# PROTOTYPE_A.net
KiCad netlist of a schematic drawn in Altium Designer
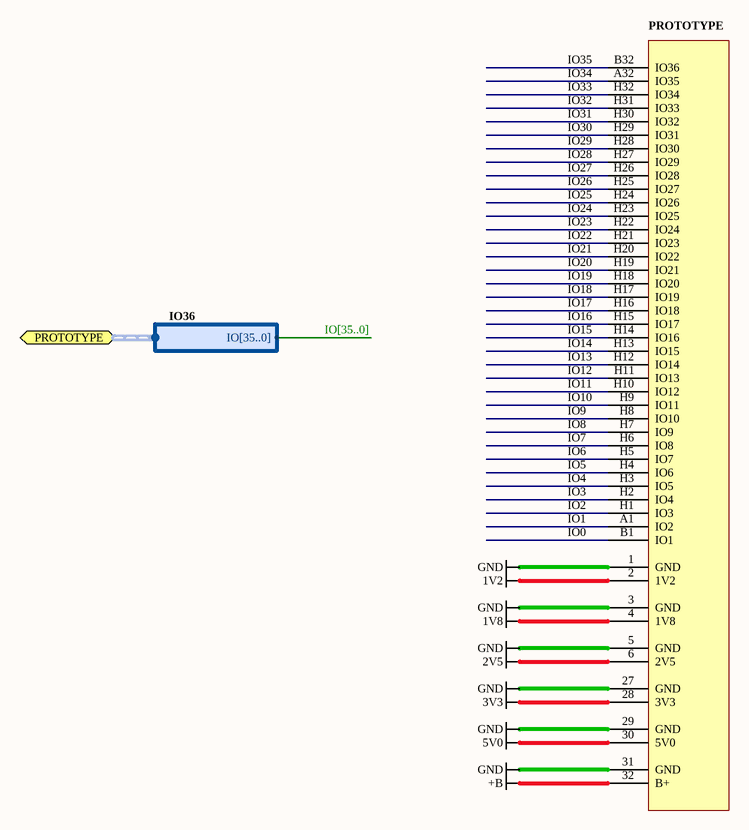
[diagram p0: PROTOTYPE_A.SchDoc]

(export (version "E")
  (design (tool "Eeschema 10.0.6"))
  (components
    (comp (ref "PROTOTYPE")
      (value "~")
      (footprint "TESTPOINT_ARRAY")
      (description "Test Point Array")
      (libsource (lib "AltiumDesignLibrary") (part "TEST-ARRAY"))
    )
  )
  (nets
    (net (code "2") (name "+B") (class "Default")
      (node (ref "PROTOTYPE") (pin "32") (pinfunction "B+_32") (pintype "power_in"))
    )
    (net (code "3") (name "/IO0") (class "Default")
      (node (ref "PROTOTYPE") (pin "B1") (pinfunction "IO1_B1") (pintype "passive"))
    )
    (net (code "4") (name "/IO1") (class "Default")
      (node (ref "PROTOTYPE") (pin "A1") (pinfunction "IO2_A1") (pintype "passive"))
    )
    (net (code "5") (name "/IO2") (class "Default")
      (node (ref "PROTOTYPE") (pin "H1") (pinfunction "IO3_H1") (pintype "passive"))
    )
    (net (code "6") (name "/IO3") (class "Default")
      (node (ref "PROTOTYPE") (pin "H2") (pinfunction "IO4_H2") (pintype "passive"))
    )
    (net (code "7") (name "/IO4") (class "Default")
      (node (ref "PROTOTYPE") (pin "H3") (pinfunction "IO5_H3") (pintype "passive"))
    )
    (net (code "8") (name "/IO5") (class "Default")
      (node (ref "PROTOTYPE") (pin "H4") (pinfunction "IO6_H4") (pintype "passive"))
    )
    (net (code "9") (name "/IO6") (class "Default")
      (node (ref "PROTOTYPE") (pin "H5") (pinfunction "IO7_H5") (pintype "passive"))
    )
    (net (code "10") (name "/IO7") (class "Default")
      (node (ref "PROTOTYPE") (pin "H6") (pinfunction "IO8_H6") (pintype "passive"))
    )
    (net (code "11") (name "/IO8") (class "Default")
      (node (ref "PROTOTYPE") (pin "H7") (pinfunction "IO9_H7") (pintype "passive"))
    )
    (net (code "12") (name "/IO9") (class "Default")
      (node (ref "PROTOTYPE") (pin "H8") (pinfunction "IO10_H8") (pintype "passive"))
    )
    (net (code "13") (name "/IO10") (class "Default")
      (node (ref "PROTOTYPE") (pin "H9") (pinfunction "IO11_H9") (pintype "passive"))
    )
    (net (code "14") (name "/IO11") (class "Default")
      (node (ref "PROTOTYPE") (pin "H10") (pinfunction "IO12_H10") (pintype "passive"))
    )
    (net (code "15") (name "/IO12") (class "Default")
      (node (ref "PROTOTYPE") (pin "H11") (pinfunction "IO13_H11") (pintype "passive"))
    )
    (net (code "16") (name "/IO13") (class "Default")
      (node (ref "PROTOTYPE") (pin "H12") (pinfunction "IO14_H12") (pintype "passive"))
    )
    (net (code "17") (name "/IO14") (class "Default")
      (node (ref "PROTOTYPE") (pin "H13") (pinfunction "IO15_H13") (pintype "passive"))
    )
    (net (code "18") (name "/IO15") (class "Default")
      (node (ref "PROTOTYPE") (pin "H14") (pinfunction "IO16_H14") (pintype "passive"))
    )
    (net (code "19") (name "/IO16") (class "Default")
      (node (ref "PROTOTYPE") (pin "H15") (pinfunction "IO17_H15") (pintype "passive"))
    )
    (net (code "20") (name "/IO17") (class "Default")
      (node (ref "PROTOTYPE") (pin "H16") (pinfunction "IO18_H16") (pintype "passive"))
    )
    (net (code "21") (name "/IO18") (class "Default")
      (node (ref "PROTOTYPE") (pin "H17") (pinfunction "IO19_H17") (pintype "passive"))
    )
    (net (code "22") (name "/IO19") (class "Default")
      (node (ref "PROTOTYPE") (pin "H18") (pinfunction "IO20_H18") (pintype "passive"))
    )
    (net (code "23") (name "/IO20") (class "Default")
      (node (ref "PROTOTYPE") (pin "H19") (pinfunction "IO21_H19") (pintype "passive"))
    )
    (net (code "24") (name "/IO21") (class "Default")
      (node (ref "PROTOTYPE") (pin "H20") (pinfunction "IO22_H20") (pintype "passive"))
    )
    (net (code "25") (name "/IO22") (class "Default")
      (node (ref "PROTOTYPE") (pin "H21") (pinfunction "IO23_H21") (pintype "passive"))
    )
    (net (code "26") (name "/IO23") (class "Default")
      (node (ref "PROTOTYPE") (pin "H22") (pinfunction "IO24_H22") (pintype "passive"))
    )
    (net (code "27") (name "/IO24") (class "Default")
      (node (ref "PROTOTYPE") (pin "H23") (pinfunction "IO25_H23") (pintype "passive"))
    )
    (net (code "28") (name "/IO25") (class "Default")
      (node (ref "PROTOTYPE") (pin "H24") (pinfunction "IO26_H24") (pintype "passive"))
    )
    (net (code "29") (name "/IO26") (class "Default")
      (node (ref "PROTOTYPE") (pin "H25") (pinfunction "IO27_H25") (pintype "passive"))
    )
    (net (code "30") (name "/IO27") (class "Default")
      (node (ref "PROTOTYPE") (pin "H26") (pinfunction "IO28_H26") (pintype "passive"))
    )
    (net (code "31") (name "/IO28") (class "Default")
      (node (ref "PROTOTYPE") (pin "H27") (pinfunction "IO29_H27") (pintype "passive"))
    )
    (net (code "32") (name "/IO29") (class "Default")
      (node (ref "PROTOTYPE") (pin "H28") (pinfunction "IO30_H28") (pintype "passive"))
    )
    (net (code "33") (name "/IO30") (class "Default")
      (node (ref "PROTOTYPE") (pin "H29") (pinfunction "IO31_H29") (pintype "passive"))
    )
    (net (code "34") (name "/IO31") (class "Default")
      (node (ref "PROTOTYPE") (pin "H30") (pinfunction "IO32_H30") (pintype "passive"))
    )
    (net (code "35") (name "/IO32") (class "Default")
      (node (ref "PROTOTYPE") (pin "H31") (pinfunction "IO33_H31") (pintype "passive"))
    )
    (net (code "36") (name "/IO33") (class "Default")
      (node (ref "PROTOTYPE") (pin "H32") (pinfunction "IO34_H32") (pintype "passive"))
    )
    (net (code "37") (name "/IO34") (class "Default")
      (node (ref "PROTOTYPE") (pin "A32") (pinfunction "IO35_A32") (pintype "passive"))
    )
    (net (code "38") (name "/IO35") (class "Default")
      (node (ref "PROTOTYPE") (pin "B32") (pinfunction "IO36_B32") (pintype "passive"))
    )
    (net (code "41") (name "1V2") (class "Default")
      (node (ref "PROTOTYPE") (pin "2") (pinfunction "1V2_2") (pintype "power_in"))
    )
    (net (code "42") (name "1V8") (class "Default")
      (node (ref "PROTOTYPE") (pin "4") (pinfunction "1V8_4") (pintype "power_in"))
    )
    (net (code "43") (name "2V5") (class "Default")
      (node (ref "PROTOTYPE") (pin "6") (pinfunction "2V5_6") (pintype "power_in"))
    )
    (net (code "44") (name "3V3") (class "Default")
      (node (ref "PROTOTYPE") (pin "28") (pinfunction "3V3_28") (pintype "power_in"))
    )
    (net (code "45") (name "5V0") (class "Default")
      (node (ref "PROTOTYPE") (pin "30") (pinfunction "5V0_30") (pintype "power_in"))
    )
    (net (code "46") (name "GND") (class "Default")
      (node (ref "PROTOTYPE") (pin "1") (pinfunction "GND_1") (pintype "power_in"))
      (node (ref "PROTOTYPE") (pin "27") (pinfunction "GND_27") (pintype "power_in"))
      (node (ref "PROTOTYPE") (pin "29") (pinfunction "GND_29") (pintype "power_in"))
      (node (ref "PROTOTYPE") (pin "3") (pinfunction "GND_3") (pintype "power_in"))
      (node (ref "PROTOTYPE") (pin "31") (pinfunction "GND_31") (pintype "power_in"))
      (node (ref "PROTOTYPE") (pin "5") (pinfunction "GND_5") (pintype "power_in"))
    )
  )
)
